# Tangga.net
KiCad netlist of a schematic drawn in EAGLE
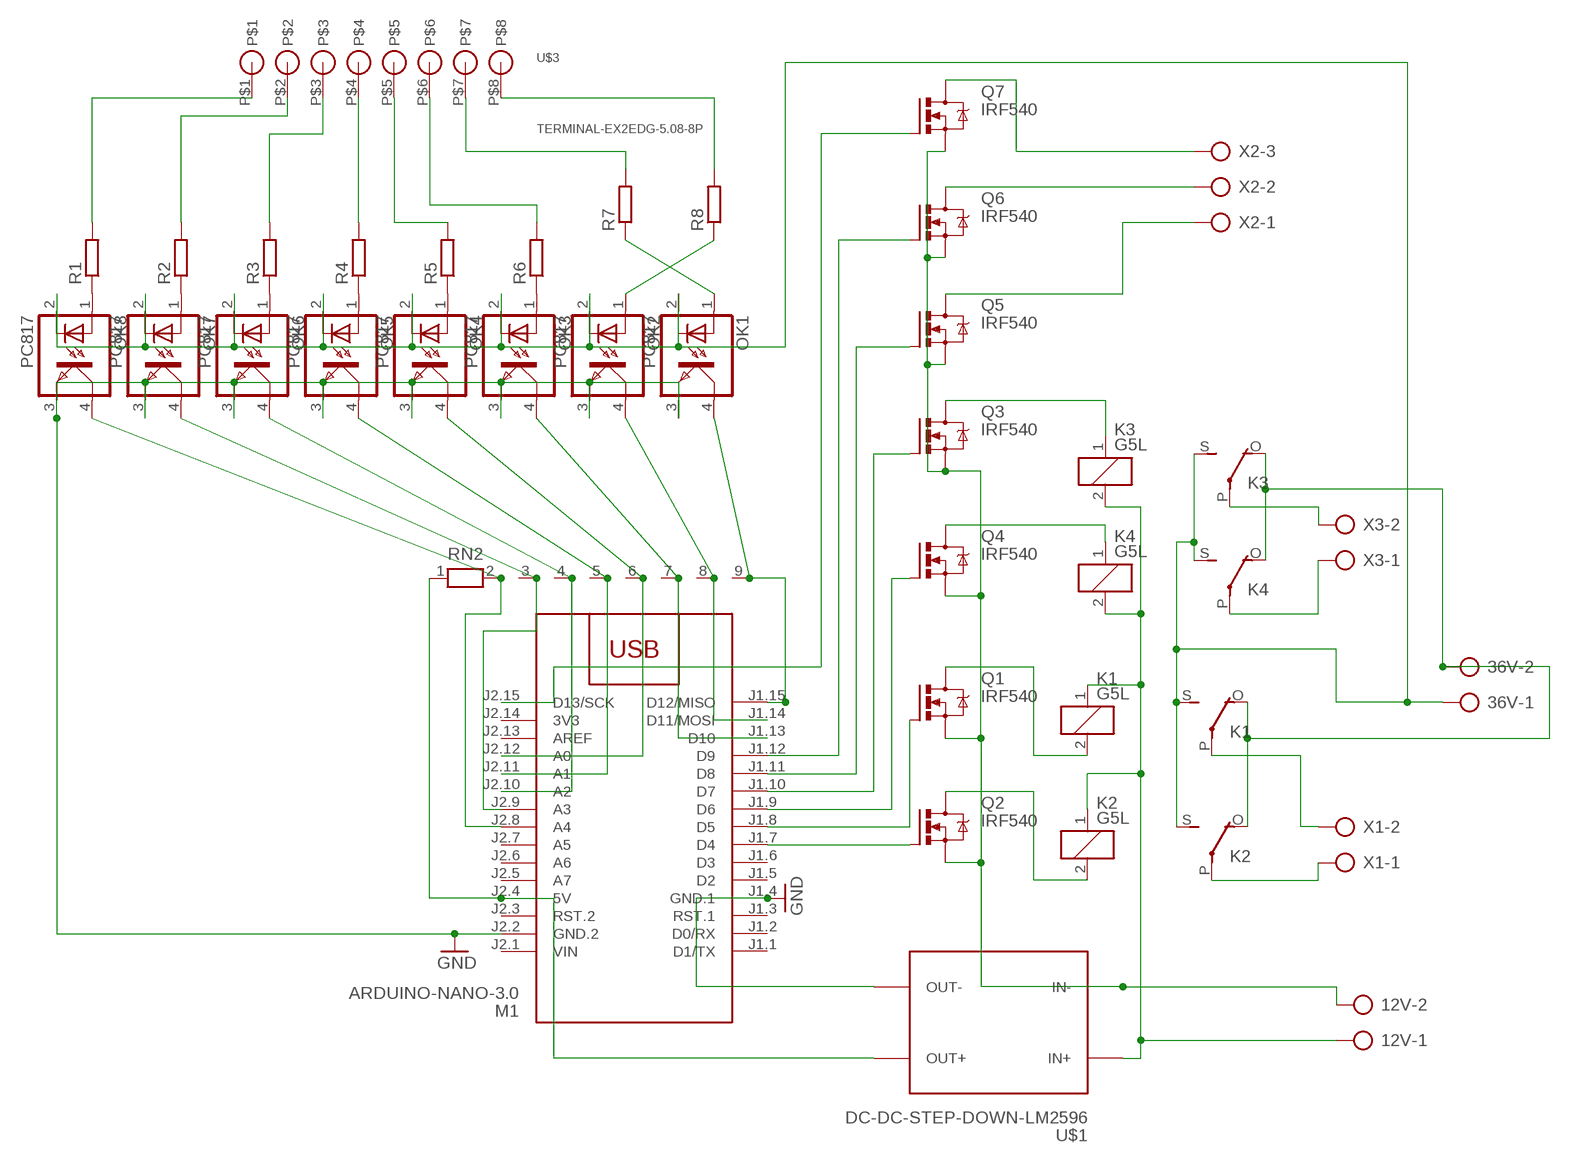
[diagram p0: schematic, sheet 1]

(export (version "E")
  (design (tool "Eeschema 10.0.6"))
  (components
    (comp (ref "12V")
      (value "AK300/2")
      (footprint "eagle-import:AK300_2")
      (libsource (lib "eagle-import") (part "AK300/2"))
    )
    (comp (ref "36V")
      (value "AK300/2")
      (footprint "eagle-import:AK300_2")
      (libsource (lib "eagle-import") (part "AK300/2"))
    )
    (comp (ref "K1")
      (value "G5L")
      (footprint "eagle-import:G5LE")
      (libsource (lib "eagle-import") (part "G5L"))
    )
    (comp (ref "K2")
      (value "G5L")
      (footprint "eagle-import:G5LE")
      (libsource (lib "eagle-import") (part "G5L"))
    )
    (comp (ref "K3")
      (value "G5L")
      (footprint "eagle-import:G5LE")
      (libsource (lib "eagle-import") (part "G5L"))
    )
    (comp (ref "K4")
      (value "G5L")
      (footprint "eagle-import:G5LE")
      (libsource (lib "eagle-import") (part "G5L"))
    )
    (comp (ref "M1")
      (value "ARDUINO-NANO-3.0")
      (footprint "eagle-import:ARDUINO-NANO-3.0")
      (libsource (lib "eagle-import") (part "ARDUINO-NANO-3.0"))
    )
    (comp (ref "OK1")
      (value "PC817")
      (footprint "eagle-import:DIL04")
      (fields (field (name "MPN") "PC817X4J000F"))
      (libsource (lib "eagle-import") (part "PC817"))
    )
    (comp (ref "OK2")
      (value "PC817")
      (footprint "eagle-import:DIL04")
      (fields (field (name "MPN") "PC817X4J000F"))
      (libsource (lib "eagle-import") (part "PC817"))
    )
    (comp (ref "OK3")
      (value "PC817")
      (footprint "eagle-import:DIL04")
      (fields (field (name "MPN") "PC817X4J000F"))
      (libsource (lib "eagle-import") (part "PC817"))
    )
    (comp (ref "OK4")
      (value "PC817")
      (footprint "eagle-import:DIL04")
      (fields (field (name "MPN") "PC817X4J000F"))
      (libsource (lib "eagle-import") (part "PC817"))
    )
    (comp (ref "OK5")
      (value "PC817")
      (footprint "eagle-import:DIL04")
      (fields (field (name "MPN") "PC817X4J000F"))
      (libsource (lib "eagle-import") (part "PC817"))
    )
    (comp (ref "OK6")
      (value "PC817")
      (footprint "eagle-import:DIL04")
      (fields (field (name "MPN") "PC817X4J000F"))
      (libsource (lib "eagle-import") (part "PC817"))
    )
    (comp (ref "OK7")
      (value "PC817")
      (footprint "eagle-import:DIL04")
      (fields (field (name "MPN") "PC817X4J000F"))
      (libsource (lib "eagle-import") (part "PC817"))
    )
    (comp (ref "OK8")
      (value "PC817")
      (footprint "eagle-import:DIL04")
      (fields (field (name "MPN") "PC817X4J000F"))
      (libsource (lib "eagle-import") (part "PC817"))
    )
    (comp (ref "Q1")
      (value "IRF540")
      (footprint "eagle-import:TO220BV")
      (libsource (lib "eagle-import") (part "IRF540"))
    )
    (comp (ref "Q2")
      (value "IRF540")
      (footprint "eagle-import:TO220BV")
      (libsource (lib "eagle-import") (part "IRF540"))
    )
    (comp (ref "Q3")
      (value "IRF540")
      (footprint "eagle-import:TO220BV")
      (libsource (lib "eagle-import") (part "IRF540"))
    )
    (comp (ref "Q4")
      (value "IRF540")
      (footprint "eagle-import:TO220BV")
      (libsource (lib "eagle-import") (part "IRF540"))
    )
    (comp (ref "Q5")
      (value "IRF540")
      (footprint "eagle-import:TO220BV")
      (libsource (lib "eagle-import") (part "IRF540"))
    )
    (comp (ref "Q6")
      (value "IRF540")
      (footprint "eagle-import:TO220BV")
      (libsource (lib "eagle-import") (part "IRF540"))
    )
    (comp (ref "Q7")
      (value "IRF540")
      (footprint "eagle-import:TO220BV")
      (libsource (lib "eagle-import") (part "IRF540"))
    )
    (comp (ref "R1")
      (value "R-EU_0204/7")
      (footprint "eagle-import:0204_7")
      (libsource (lib "eagle-import") (part "R-EU_0204/7"))
    )
    (comp (ref "R2")
      (value "R-EU_0204/7")
      (footprint "eagle-import:0204_7")
      (libsource (lib "eagle-import") (part "R-EU_0204/7"))
    )
    (comp (ref "R3")
      (value "R-EU_0204/7")
      (footprint "eagle-import:0204_7")
      (libsource (lib "eagle-import") (part "R-EU_0204/7"))
    )
    (comp (ref "R4")
      (value "R-EU_0204/7")
      (footprint "eagle-import:0204_7")
      (libsource (lib "eagle-import") (part "R-EU_0204/7"))
    )
    (comp (ref "R5")
      (value "R-EU_0204/7")
      (footprint "eagle-import:0204_7")
      (libsource (lib "eagle-import") (part "R-EU_0204/7"))
    )
    (comp (ref "R6")
      (value "R-EU_0204/7")
      (footprint "eagle-import:0204_7")
      (libsource (lib "eagle-import") (part "R-EU_0204/7"))
    )
    (comp (ref "R7")
      (value "R-EU_0204/7")
      (footprint "eagle-import:0204_7")
      (libsource (lib "eagle-import") (part "R-EU_0204/7"))
    )
    (comp (ref "R8")
      (value "R-EU_0204/7")
      (footprint "eagle-import:0204_7")
      (libsource (lib "eagle-import") (part "R-EU_0204/7"))
    )
    (comp (ref "RN2")
      (value "RN08")
      (footprint "eagle-import:RN-9")
      (libsource (lib "eagle-import") (part "RN08"))
    )
    (comp (ref "U$1")
      (value "DC-DC-STEP-DOWN-LM2596")
      (footprint "eagle-import:DC-DC-STEP-DOWN-LM2596")
      (libsource (lib "eagle-import") (part "DC-DC-STEP-DOWN-LM2596"))
    )
    (comp (ref "U$3")
      (value "TERMINAL-EX2EDG-5.08-8P")
      (footprint "eagle-import:8P")
      (libsource (lib "eagle-import") (part "TERMINAL-EX2EDG-5.08-8P"))
    )
    (comp (ref "X1")
      (value "AK300/2")
      (footprint "eagle-import:AK300_2")
      (libsource (lib "eagle-import") (part "AK300/2"))
    )
    (comp (ref "X2")
      (value "AK300/3")
      (footprint "eagle-import:AK300_3")
      (libsource (lib "eagle-import") (part "AK300/3"))
    )
    (comp (ref "X3")
      (value "AK300/2")
      (footprint "eagle-import:AK300_2")
      (libsource (lib "eagle-import") (part "AK300/2"))
    )
  )
  (nets
    (net (code "1") (name "/3V3") (class "Default")
      (node (ref "M1") (pin "J2.14") (pinfunction "3V3_J2.14") (pintype "power_in"))
    )
    (net (code "2") (name "/VIN") (class "Default")
      (node (ref "M1") (pin "J2.1") (pinfunction "VIN_J2.1") (pintype "power_in"))
    )
    (net (code "3") (name "GND") (class "Default")
      (node (ref "M1") (pin "J1.4") (pinfunction "GND.1_J1.4") (pintype "power_in"))
      (node (ref "M1") (pin "J2.2") (pinfunction "GND.2_J2.2") (pintype "power_in"))
      (node (ref "OK1") (pin "3") (pinfunction "EMIT_3") (pintype "passive"))
      (node (ref "OK2") (pin "3") (pinfunction "EMIT_3") (pintype "passive"))
      (node (ref "OK3") (pin "3") (pinfunction "EMIT_3") (pintype "passive"))
      (node (ref "OK4") (pin "3") (pinfunction "EMIT_3") (pintype "passive"))
      (node (ref "OK5") (pin "3") (pinfunction "EMIT_3") (pintype "passive"))
      (node (ref "OK6") (pin "3") (pinfunction "EMIT_3") (pintype "passive"))
      (node (ref "OK7") (pin "3") (pinfunction "EMIT_3") (pintype "passive"))
      (node (ref "OK8") (pin "3") (pinfunction "EMIT_3") (pintype "passive"))
      (node (ref "U$1") (pin "OUT-") (pinfunction "OUT-_OUT-") (pintype "bidirectional"))
    )
    (net (code "4") (name "Net-(12VA-KL)") (class "Default")
      (node (ref "12V") (pin "1") (pinfunction "KL_1") (pintype "passive"))
      (node (ref "K1") (pin "1") (pinfunction "1_1") (pintype "passive"))
      (node (ref "K2") (pin "1") (pinfunction "1_1") (pintype "passive"))
      (node (ref "K3") (pin "2") (pinfunction "2_2") (pintype "passive"))
      (node (ref "K4") (pin "2") (pinfunction "2_2") (pintype "passive"))
      (node (ref "U$1") (pin "IN+") (pinfunction "IN+_IN+") (pintype "bidirectional"))
    )
    (net (code "5") (name "Net-(12VB-KL)") (class "Default")
      (node (ref "12V") (pin "2") (pinfunction "KL_2") (pintype "passive"))
      (node (ref "Q1") (pin "S") (pinfunction "S_S") (pintype "passive"))
      (node (ref "Q2") (pin "S") (pinfunction "S_S") (pintype "passive"))
      (node (ref "Q3") (pin "S") (pinfunction "S_S") (pintype "passive"))
      (node (ref "Q4") (pin "S") (pinfunction "S_S") (pintype "passive"))
      (node (ref "Q5") (pin "S") (pinfunction "S_S") (pintype "passive"))
      (node (ref "Q6") (pin "S") (pinfunction "S_S") (pintype "passive"))
      (node (ref "Q7") (pin "S") (pinfunction "S_S") (pintype "passive"))
      (node (ref "U$1") (pin "IN-") (pinfunction "IN-_IN-") (pintype "bidirectional"))
    )
    (net (code "6") (name "Net-(36VA-KL)") (class "Default")
      (node (ref "36V") (pin "1") (pinfunction "KL_1") (pintype "passive"))
      (node (ref "K1") (pin "S") (pinfunction "S_S") (pintype "passive"))
      (node (ref "K2") (pin "S") (pinfunction "S_S") (pintype "passive"))
      (node (ref "K3") (pin "S") (pinfunction "S_S") (pintype "passive"))
      (node (ref "K4") (pin "S") (pinfunction "S_S") (pintype "passive"))
      (node (ref "OK1") (pin "2") (pinfunction "C_2") (pintype "passive"))
      (node (ref "OK2") (pin "2") (pinfunction "C_2") (pintype "passive"))
      (node (ref "OK3") (pin "2") (pinfunction "C_2") (pintype "passive"))
      (node (ref "OK4") (pin "2") (pinfunction "C_2") (pintype "passive"))
      (node (ref "OK5") (pin "2") (pinfunction "C_2") (pintype "passive"))
      (node (ref "OK6") (pin "2") (pinfunction "C_2") (pintype "passive"))
      (node (ref "OK7") (pin "2") (pinfunction "C_2") (pintype "passive"))
      (node (ref "OK8") (pin "2") (pinfunction "C_2") (pintype "passive"))
    )
    (net (code "7") (name "Net-(36VB-KL)") (class "Default")
      (node (ref "36V") (pin "2") (pinfunction "KL_2") (pintype "passive"))
      (node (ref "K1") (pin "O") (pinfunction "O_O") (pintype "passive"))
      (node (ref "K2") (pin "O") (pinfunction "O_O") (pintype "passive"))
      (node (ref "K3") (pin "O") (pinfunction "O_O") (pintype "passive"))
      (node (ref "K4") (pin "O") (pinfunction "O_O") (pintype "passive"))
    )
    (net (code "8") (name "Net-(K1-Pad2)") (class "Default")
      (node (ref "K1") (pin "2") (pinfunction "2_2") (pintype "passive"))
      (node (ref "Q1") (pin "D") (pinfunction "D_D") (pintype "passive"))
    )
    (net (code "9") (name "Net-(K2-Pad2)") (class "Default")
      (node (ref "K2") (pin "2") (pinfunction "2_2") (pintype "passive"))
      (node (ref "Q2") (pin "D") (pinfunction "D_D") (pintype "passive"))
    )
    (net (code "10") (name "Net-(K3-Pad1)") (class "Default")
      (node (ref "K3") (pin "1") (pinfunction "1_1") (pintype "passive"))
      (node (ref "Q3") (pin "D") (pinfunction "D_D") (pintype "passive"))
    )
    (net (code "11") (name "Net-(K4-Pad1)") (class "Default")
      (node (ref "K4") (pin "1") (pinfunction "1_1") (pintype "passive"))
      (node (ref "Q4") (pin "D") (pinfunction "D_D") (pintype "passive"))
    )
    (net (code "12") (name "Net-(M1-5V)") (class "Default")
      (node (ref "M1") (pin "J2.4") (pinfunction "5V_J2.4") (pintype "power_in"))
      (node (ref "RN2") (pin "1") (pinfunction "1_1") (pintype "passive"))
      (node (ref "U$1") (pin "OUT+") (pinfunction "OUT+_OUT+") (pintype "bidirectional"))
    )
    (net (code "13") (name "Net-(M1-A0)") (class "Default")
      (node (ref "M1") (pin "J2.12") (pinfunction "A0_J2.12") (pintype "bidirectional"))
      (node (ref "OK4") (pin "4") (pinfunction "COL_4") (pintype "passive"))
      (node (ref "RN2") (pin "6") (pinfunction "6_6") (pintype "passive"))
    )
    (net (code "14") (name "Net-(M1-A1)") (class "Default")
      (node (ref "M1") (pin "J2.11") (pinfunction "A1_J2.11") (pintype "bidirectional"))
      (node (ref "OK5") (pin "4") (pinfunction "COL_4") (pintype "passive"))
      (node (ref "RN2") (pin "5") (pinfunction "5_5") (pintype "passive"))
    )
    (net (code "15") (name "Net-(M1-A2)") (class "Default")
      (node (ref "M1") (pin "J2.10") (pinfunction "A2_J2.10") (pintype "bidirectional"))
      (node (ref "OK6") (pin "4") (pinfunction "COL_4") (pintype "passive"))
      (node (ref "RN2") (pin "4") (pinfunction "4_4") (pintype "passive"))
    )
    (net (code "16") (name "Net-(M1-A3)") (class "Default")
      (node (ref "M1") (pin "J2.9") (pinfunction "A3_J2.9") (pintype "bidirectional"))
      (node (ref "OK7") (pin "4") (pinfunction "COL_4") (pintype "passive"))
      (node (ref "RN2") (pin "3") (pinfunction "3_3") (pintype "passive"))
    )
    (net (code "17") (name "Net-(M1-A4)") (class "Default")
      (node (ref "M1") (pin "J2.8") (pinfunction "A4_J2.8") (pintype "bidirectional"))
      (node (ref "OK8") (pin "4") (pinfunction "COL_4") (pintype "passive"))
      (node (ref "RN2") (pin "2") (pinfunction "2_2") (pintype "passive"))
    )
    (net (code "18") (name "Net-(M1-D4)") (class "Default")
      (node (ref "M1") (pin "J1.7") (pinfunction "D4_J1.7") (pintype "bidirectional"))
      (node (ref "Q2") (pin "G") (pinfunction "G_G") (pintype "passive"))
    )
    (net (code "19") (name "Net-(M1-D5)") (class "Default")
      (node (ref "M1") (pin "J1.8") (pinfunction "D5_J1.8") (pintype "bidirectional"))
      (node (ref "Q1") (pin "G") (pinfunction "G_G") (pintype "passive"))
    )
    (net (code "20") (name "Net-(M1-D6)") (class "Default")
      (node (ref "M1") (pin "J1.9") (pinfunction "D6_J1.9") (pintype "bidirectional"))
      (node (ref "Q4") (pin "G") (pinfunction "G_G") (pintype "passive"))
    )
    (net (code "21") (name "Net-(M1-D7)") (class "Default")
      (node (ref "M1") (pin "J1.10") (pinfunction "D7_J1.10") (pintype "bidirectional"))
      (node (ref "Q3") (pin "G") (pinfunction "G_G") (pintype "passive"))
    )
    (net (code "22") (name "Net-(M1-D8)") (class "Default")
      (node (ref "M1") (pin "J1.11") (pinfunction "D8_J1.11") (pintype "bidirectional"))
      (node (ref "Q5") (pin "G") (pinfunction "G_G") (pintype "passive"))
    )
    (net (code "23") (name "Net-(M1-D9)") (class "Default")
      (node (ref "M1") (pin "J1.12") (pinfunction "D9_J1.12") (pintype "bidirectional"))
      (node (ref "Q6") (pin "G") (pinfunction "G_G") (pintype "passive"))
    )
    (net (code "24") (name "Net-(M1-D10)") (class "Default")
      (node (ref "M1") (pin "J1.13") (pinfunction "D10_J1.13") (pintype "bidirectional"))
      (node (ref "OK3") (pin "4") (pinfunction "COL_4") (pintype "passive"))
      (node (ref "RN2") (pin "7") (pinfunction "7_7") (pintype "passive"))
    )
    (net (code "25") (name "Net-(M1-D11{slash}MOSI)") (class "Default")
      (node (ref "M1") (pin "J1.14") (pinfunction "D11/MOSI_J1.14") (pintype "bidirectional"))
      (node (ref "OK2") (pin "4") (pinfunction "COL_4") (pintype "passive"))
      (node (ref "RN2") (pin "8") (pinfunction "8_8") (pintype "passive"))
    )
    (net (code "26") (name "Net-(M1-D12{slash}MISO)") (class "Default")
      (node (ref "M1") (pin "J1.15") (pinfunction "D12/MISO_J1.15") (pintype "bidirectional"))
      (node (ref "OK1") (pin "4") (pinfunction "COL_4") (pintype "passive"))
      (node (ref "RN2") (pin "9") (pinfunction "9_9") (pintype "passive"))
    )
    (net (code "27") (name "Net-(M1-D13{slash}SCK)") (class "Default")
      (node (ref "M1") (pin "J2.15") (pinfunction "D13/SCK_J2.15") (pintype "bidirectional"))
      (node (ref "Q7") (pin "G") (pinfunction "G_G") (pintype "passive"))
    )
    (net (code "28") (name "Net-(OK1-A)") (class "Default")
      (node (ref "OK1") (pin "1") (pinfunction "A_1") (pintype "passive"))
      (node (ref "R7") (pin "1") (pinfunction "1_1") (pintype "passive"))
    )
    (net (code "29") (name "Net-(OK2-A)") (class "Default")
      (node (ref "OK2") (pin "1") (pinfunction "A_1") (pintype "passive"))
      (node (ref "R8") (pin "1") (pinfunction "1_1") (pintype "passive"))
    )
    (net (code "30") (name "Net-(OK3-A)") (class "Default")
      (node (ref "OK3") (pin "1") (pinfunction "A_1") (pintype "passive"))
      (node (ref "R6") (pin "1") (pinfunction "1_1") (pintype "passive"))
    )
    (net (code "31") (name "Net-(OK4-A)") (class "Default")
      (node (ref "OK4") (pin "1") (pinfunction "A_1") (pintype "passive"))
      (node (ref "R5") (pin "1") (pinfunction "1_1") (pintype "passive"))
    )
    (net (code "32") (name "Net-(OK5-A)") (class "Default")
      (node (ref "OK5") (pin "1") (pinfunction "A_1") (pintype "passive"))
      (node (ref "R4") (pin "1") (pinfunction "1_1") (pintype "passive"))
    )
    (net (code "33") (name "Net-(OK6-A)") (class "Default")
      (node (ref "OK6") (pin "1") (pinfunction "A_1") (pintype "passive"))
      (node (ref "R3") (pin "1") (pinfunction "1_1") (pintype "passive"))
    )
    (net (code "34") (name "Net-(OK7-A)") (class "Default")
      (node (ref "OK7") (pin "1") (pinfunction "A_1") (pintype "passive"))
      (node (ref "R2") (pin "1") (pinfunction "1_1") (pintype "passive"))
    )
    (net (code "35") (name "Net-(OK8-A)") (class "Default")
      (node (ref "OK8") (pin "1") (pinfunction "A_1") (pintype "passive"))
      (node (ref "R1") (pin "1") (pinfunction "1_1") (pintype "passive"))
    )
    (net (code "36") (name "Net-(R1-Pad2)") (class "Default")
      (node (ref "R1") (pin "2") (pinfunction "2_2") (pintype "passive"))
      (node (ref "U$3") (pin "P$1") (pinfunction "P$1_P$1") (pintype "bidirectional"))
    )
    (net (code "37") (name "Net-(R2-Pad2)") (class "Default")
      (node (ref "R2") (pin "2") (pinfunction "2_2") (pintype "passive"))
      (node (ref "U$3") (pin "P$2") (pinfunction "P$2_P$2") (pintype "bidirectional"))
    )
    (net (code "38") (name "Net-(R3-Pad2)") (class "Default")
      (node (ref "R3") (pin "2") (pinfunction "2_2") (pintype "passive"))
      (node (ref "U$3") (pin "P$3") (pinfunction "P$3_P$3") (pintype "bidirectional"))
    )
    (net (code "39") (name "Net-(R4-Pad2)") (class "Default")
      (node (ref "R4") (pin "2") (pinfunction "2_2") (pintype "passive"))
      (node (ref "U$3") (pin "P$4") (pinfunction "P$4_P$4") (pintype "bidirectional"))
    )
    (net (code "40") (name "Net-(R5-Pad2)") (class "Default")
      (node (ref "R5") (pin "2") (pinfunction "2_2") (pintype "passive"))
      (node (ref "U$3") (pin "P$5") (pinfunction "P$5_P$5") (pintype "bidirectional"))
    )
    (net (code "41") (name "Net-(R6-Pad2)") (class "Default")
      (node (ref "R6") (pin "2") (pinfunction "2_2") (pintype "passive"))
      (node (ref "U$3") (pin "P$6") (pinfunction "P$6_P$6") (pintype "bidirectional"))
    )
    (net (code "42") (name "Net-(R7-Pad2)") (class "Default")
      (node (ref "R7") (pin "2") (pinfunction "2_2") (pintype "passive"))
      (node (ref "U$3") (pin "P$7") (pinfunction "P$7_P$7") (pintype "bidirectional"))
    )
    (net (code "43") (name "Net-(R8-Pad2)") (class "Default")
      (node (ref "R8") (pin "2") (pinfunction "2_2") (pintype "passive"))
      (node (ref "U$3") (pin "P$8") (pinfunction "P$8_P$8") (pintype "bidirectional"))
    )
    (net (code "44") (name "Net-(X1A-KL)") (class "Default")
      (node (ref "K2") (pin "P") (pinfunction "P_P") (pintype "passive"))
      (node (ref "X1") (pin "1") (pinfunction "KL_1") (pintype "passive"))
    )
    (net (code "45") (name "Net-(X1B-KL)") (class "Default")
      (node (ref "K1") (pin "P") (pinfunction "P_P") (pintype "passive"))
      (node (ref "X1") (pin "2") (pinfunction "KL_2") (pintype "passive"))
    )
    (net (code "46") (name "Net-(X2A-KL)") (class "Default")
      (node (ref "Q5") (pin "D") (pinfunction "D_D") (pintype "passive"))
      (node (ref "X2") (pin "1") (pinfunction "KL_1") (pintype "passive"))
    )
    (net (code "47") (name "Net-(X2B-KL)") (class "Default")
      (node (ref "Q6") (pin "D") (pinfunction "D_D") (pintype "passive"))
      (node (ref "X2") (pin "2") (pinfunction "KL_2") (pintype "passive"))
    )
    (net (code "48") (name "Net-(X2C-KL)") (class "Default")
      (node (ref "Q7") (pin "D") (pinfunction "D_D") (pintype "passive"))
      (node (ref "X2") (pin "3") (pinfunction "KL_3") (pintype "passive"))
    )
    (net (code "49") (name "Net-(X3A-KL)") (class "Default")
      (node (ref "K4") (pin "P") (pinfunction "P_P") (pintype "passive"))
      (node (ref "X3") (pin "1") (pinfunction "KL_1") (pintype "passive"))
    )
    (net (code "50") (name "Net-(X3B-KL)") (class "Default")
      (node (ref "K3") (pin "P") (pinfunction "P_P") (pintype "passive"))
      (node (ref "X3") (pin "2") (pinfunction "KL_2") (pintype "passive"))
    )
    (net (code "51") (name "unconnected-(M1-A5-PadJ2.7)") (class "Default")
      (node (ref "M1") (pin "J2.7") (pinfunction "A5_J2.7") (pintype "bidirectional"))
    )
    (net (code "52") (name "unconnected-(M1-A6-PadJ2.6)") (class "Default")
      (node (ref "M1") (pin "J2.6") (pinfunction "A6_J2.6") (pintype "bidirectional"))
    )
    (net (code "53") (name "unconnected-(M1-A7-PadJ2.5)") (class "Default")
      (node (ref "M1") (pin "J2.5") (pinfunction "A7_J2.5") (pintype "bidirectional"))
    )
    (net (code "54") (name "unconnected-(M1-AREF-PadJ2.13)") (class "Default")
      (node (ref "M1") (pin "J2.13") (pinfunction "AREF_J2.13") (pintype "bidirectional"))
    )
    (net (code "55") (name "unconnected-(M1-D0{slash}RX-PadJ1.2)") (class "Default")
      (node (ref "M1") (pin "J1.2") (pinfunction "D0/RX_J1.2") (pintype "bidirectional"))
    )
    (net (code "56") (name "unconnected-(M1-D1{slash}TX-PadJ1.1)") (class "Default")
      (node (ref "M1") (pin "J1.1") (pinfunction "D1/TX_J1.1") (pintype "bidirectional"))
    )
    (net (code "57") (name "unconnected-(M1-D2-PadJ1.5)") (class "Default")
      (node (ref "M1") (pin "J1.5") (pinfunction "D2_J1.5") (pintype "bidirectional"))
    )
    (net (code "58") (name "unconnected-(M1-D3-PadJ1.6)") (class "Default")
      (node (ref "M1") (pin "J1.6") (pinfunction "D3_J1.6") (pintype "bidirectional"))
    )
    (net (code "59") (name "unconnected-(M1-RST.1-PadJ1.3)") (class "Default")
      (node (ref "M1") (pin "J1.3") (pinfunction "RST.1_J1.3") (pintype "bidirectional"))
    )
    (net (code "60") (name "unconnected-(M1-RST.2-PadJ2.3)") (class "Default")
      (node (ref "M1") (pin "J2.3") (pinfunction "RST.2_J2.3") (pintype "bidirectional"))
    )
  )
)
